# alarm_lamp.net
KiCad netlist of a schematic drawn in EAGLE
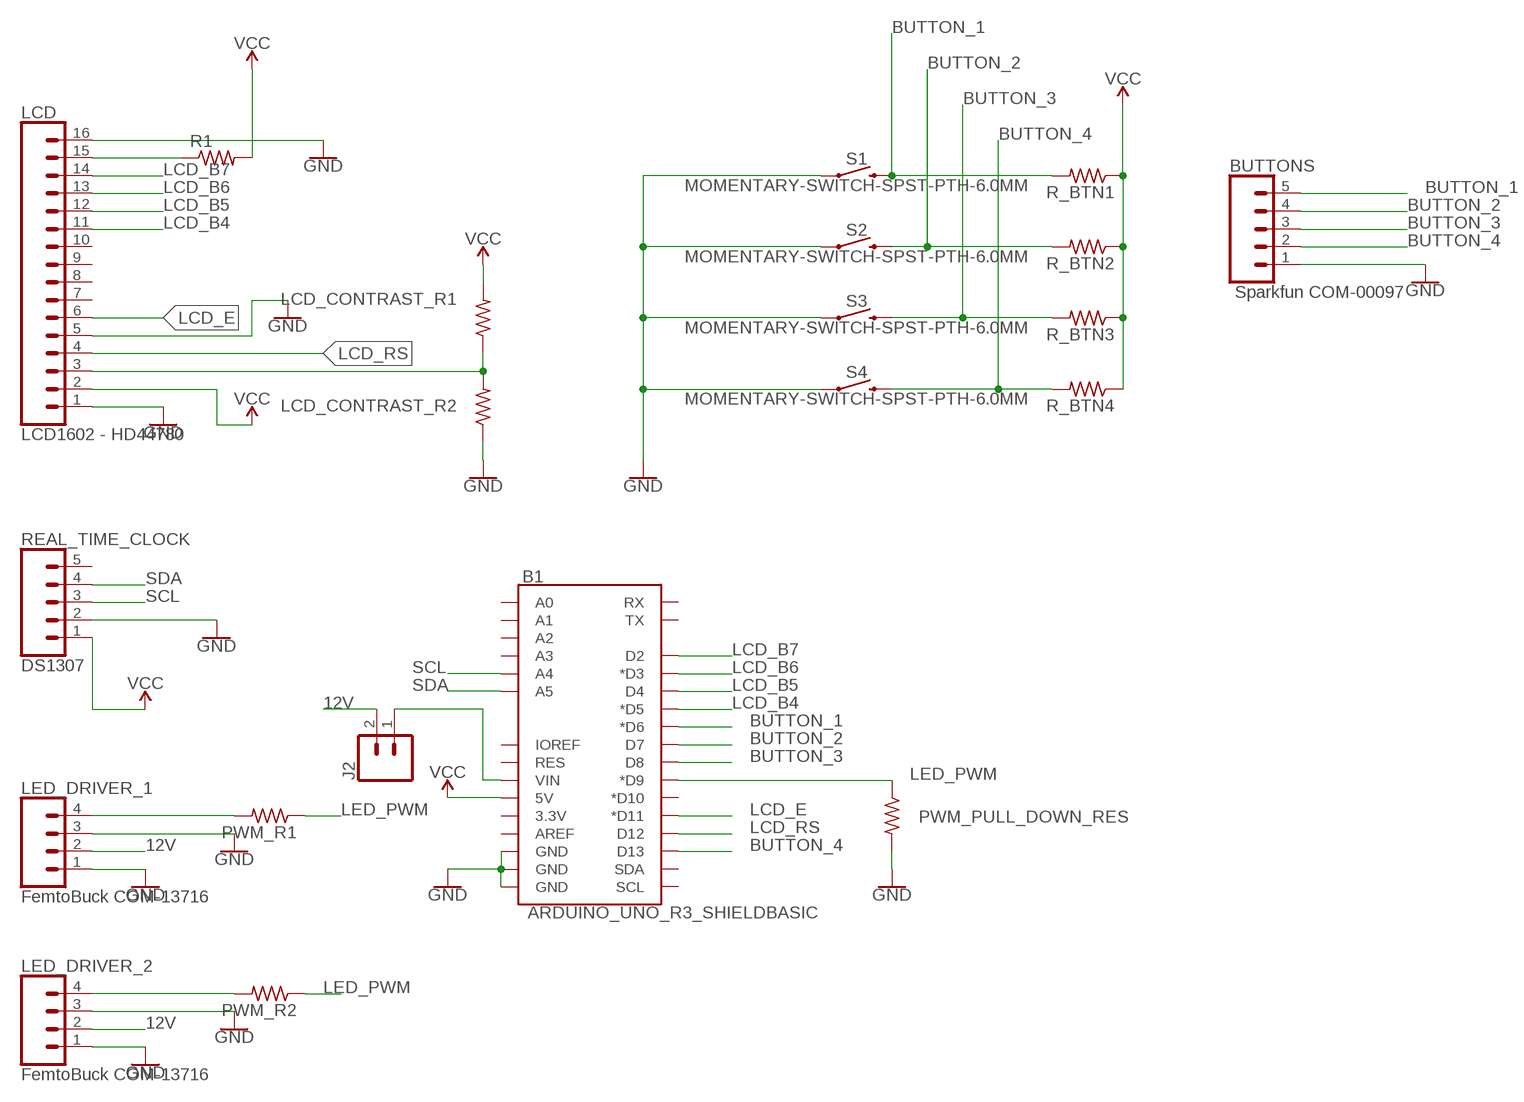
[diagram p0: schematic, sheet 1]
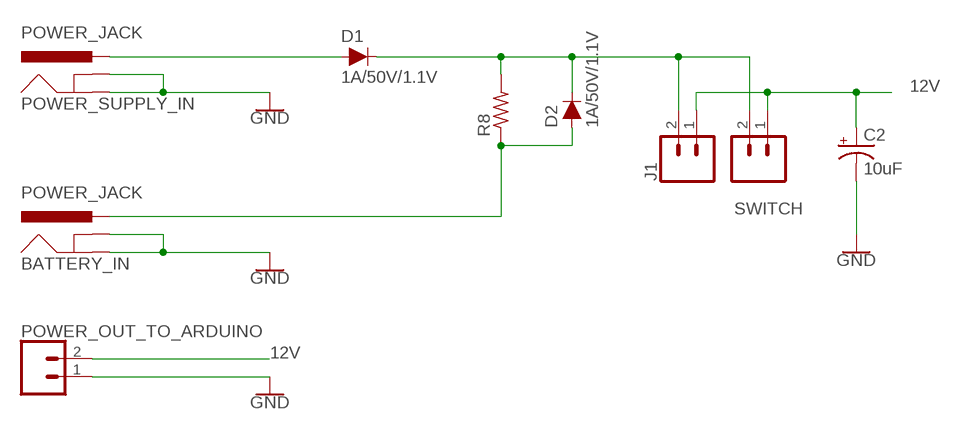
[diagram p1: schematic, sheet 2]

(export (version "E")
  (design (tool "Eeschema 10.0.6"))
  (components
    (comp (ref "B1")
      (value "ARDUINO_UNO_R3_SHIELDBASIC")
      (footprint "eagle-import:UNO_R3_SHIELD")
      (libsource (lib "eagle-import") (part "ARDUINO_UNO_R3_SHIELDBASIC"))
    )
    (comp (ref "BUTTONS")
      (value "Sparkfun COM-00097")
      (footprint "eagle-import:1X05")
      (libsource (lib "eagle-import") (part "CONN_05"))
    )
    (comp (ref "J2")
      (value "CONN_02")
      (footprint "eagle-import:1X02")
      (libsource (lib "eagle-import") (part "CONN_02"))
    )
    (comp (ref "LCD")
      (value "LCD1602 - HD44780")
      (footprint "eagle-import:1X16")
      (libsource (lib "eagle-import") (part "CONN_16"))
    )
    (comp (ref "LCD_CONTRAST_R1")
      (value "R-US_0207/9")
      (footprint "eagle-import:0207_9")
      (libsource (lib "eagle-import") (part "R-US_0207/9"))
    )
    (comp (ref "LCD_CONTRAST_R2")
      (value "R-US_0207/9")
      (footprint "eagle-import:0207_9")
      (libsource (lib "eagle-import") (part "R-US_0207/9"))
    )
    (comp (ref "LED_DRIVER_1")
      (value "FemtoBuck COM-13716")
      (footprint "eagle-import:1X04")
      (libsource (lib "eagle-import") (part "CONN_04"))
    )
    (comp (ref "LED_DRIVER_2")
      (value "FemtoBuck COM-13716")
      (footprint "eagle-import:1X04")
      (libsource (lib "eagle-import") (part "CONN_04"))
    )
    (comp (ref "PWM_PULL_DOWN_RES")
      (value "R-US_0207/9")
      (footprint "eagle-import:0207_9")
      (libsource (lib "eagle-import") (part "R-US_0207/9"))
    )
    (comp (ref "PWM_R1")
      (value "R-US_0207/9")
      (footprint "eagle-import:0207_9")
      (libsource (lib "eagle-import") (part "R-US_0207/9"))
    )
    (comp (ref "PWM_R2")
      (value "R-US_0207/9")
      (footprint "eagle-import:0207_9")
      (libsource (lib "eagle-import") (part "R-US_0207/9"))
    )
    (comp (ref "R1")
      (value "R-US_0207/9")
      (footprint "eagle-import:0207_9")
      (libsource (lib "eagle-import") (part "R-US_0207/9"))
    )
    (comp (ref "REAL_TIME_CLOCK")
      (value "DS1307")
      (footprint "eagle-import:1X05")
      (libsource (lib "eagle-import") (part "CONN_05"))
    )
    (comp (ref "R_BTN1")
      (value "R-US_0207/9")
      (footprint "eagle-import:0207_9")
      (libsource (lib "eagle-import") (part "R-US_0207/9"))
    )
    (comp (ref "R_BTN2")
      (value "R-US_0207/9")
      (footprint "eagle-import:0207_9")
      (libsource (lib "eagle-import") (part "R-US_0207/9"))
    )
    (comp (ref "R_BTN3")
      (value "R-US_0207/9")
      (footprint "eagle-import:0207_9")
      (libsource (lib "eagle-import") (part "R-US_0207/9"))
    )
    (comp (ref "R_BTN4")
      (value "R-US_0207/9")
      (footprint "eagle-import:0207_9")
      (libsource (lib "eagle-import") (part "R-US_0207/9"))
    )
    (comp (ref "S1")
      (value "MOMENTARY-SWITCH-SPST-PTH-6.0MM")
      (footprint "eagle-import:TACTILE_SWITCH_PTH_6.0MM")
      (libsource (lib "eagle-import") (part "MOMENTARY-SWITCH-SPST-PTH-6.0MM"))
    )
    (comp (ref "S2")
      (value "MOMENTARY-SWITCH-SPST-PTH-6.0MM")
      (footprint "eagle-import:TACTILE_SWITCH_PTH_6.0MM")
      (libsource (lib "eagle-import") (part "MOMENTARY-SWITCH-SPST-PTH-6.0MM"))
    )
    (comp (ref "S3")
      (value "MOMENTARY-SWITCH-SPST-PTH-6.0MM")
      (footprint "eagle-import:TACTILE_SWITCH_PTH_6.0MM")
      (libsource (lib "eagle-import") (part "MOMENTARY-SWITCH-SPST-PTH-6.0MM"))
    )
    (comp (ref "S4")
      (value "MOMENTARY-SWITCH-SPST-PTH-6.0MM")
      (footprint "eagle-import:TACTILE_SWITCH_PTH_6.0MM")
      (libsource (lib "eagle-import") (part "MOMENTARY-SWITCH-SPST-PTH-6.0MM"))
    )
    (comp (ref "BATTERY_IN")
      (value "POWER_JACK")
      (footprint "eagle-import:POWER_JACK_PTH")
      (libsource (lib "eagle-import") (part "POWER_JACK"))
    )
    (comp (ref "C2")
      (value "10uF")
      (footprint "eagle-import:CPOL-RADIAL-2.5MM-5MM")
      (libsource (lib "eagle-import") (part "10UF-POLAR-RADIAL-2.5MM-25V-20%"))
    )
    (comp (ref "D1")
      (value "1A/50V/1.1V")
      (footprint "eagle-import:DIODE-1N4001")
      (libsource (lib "eagle-import") (part "DIODE-PTH"))
    )
    (comp (ref "D2")
      (value "1A/50V/1.1V")
      (footprint "eagle-import:DIODE-1N4001")
      (libsource (lib "eagle-import") (part "DIODE-PTH"))
    )
    (comp (ref "J1")
      (value "CONN_02")
      (footprint "eagle-import:1X02")
      (libsource (lib "eagle-import") (part "CONN_02"))
    )
    (comp (ref "POWER_OUT_TO_ARDUINO")
      (value "CONN_023.5MM")
      (footprint "eagle-import:SCREWTERMINAL-3.5MM-2")
      (libsource (lib "eagle-import") (part "CONN_023.5MM"))
    )
    (comp (ref "POWER_SUPPLY_IN")
      (value "POWER_JACK")
      (footprint "eagle-import:POWER_JACK_PTH")
      (libsource (lib "eagle-import") (part "POWER_JACK"))
    )
    (comp (ref "R8")
      (value "R-US_0207/9")
      (footprint "eagle-import:0207_9")
      (libsource (lib "eagle-import") (part "R-US_0207/9"))
    )
    (comp (ref "SWITCH")
      (value "CONN_023.5MM")
      (footprint "eagle-import:SCREWTERMINAL-3.5MM-2")
      (libsource (lib "eagle-import") (part "CONN_023.5MM"))
    )
  )
  (nets
    (net (code "1") (name "12V") (class "Default")
      (node (ref "C2") (pin "1") (pinfunction "+_1") (pintype "passive"))
      (node (ref "J1") (pin "1") (pinfunction "1_1") (pintype "passive"))
      (node (ref "J2") (pin "2") (pinfunction "2_2") (pintype "passive"))
      (node (ref "LED_DRIVER_1") (pin "2") (pinfunction "2_2") (pintype "passive"))
      (node (ref "LED_DRIVER_2") (pin "2") (pinfunction "2_2") (pintype "passive"))
      (node (ref "POWER_OUT_TO_ARDUINO") (pin "2") (pinfunction "2_2") (pintype "passive"))
      (node (ref "SWITCH") (pin "1") (pinfunction "1_1") (pintype "passive"))
    )
    (net (code "2") (name "BUTTON_1") (class "Default")
      (node (ref "B1") (pin "D6") (pinfunction "*D6_D6") (pintype "bidirectional"))
      (node (ref "BUTTONS") (pin "5") (pinfunction "5_5") (pintype "passive"))
      (node (ref "R_BTN1") (pin "2") (pinfunction "2_2") (pintype "passive"))
      (node (ref "S1") (pin "3") (pinfunction "2_3") (pintype "passive"))
    )
    (net (code "3") (name "BUTTON_2") (class "Default")
      (node (ref "B1") (pin "D7") (pinfunction "D7_D7") (pintype "bidirectional"))
      (node (ref "BUTTONS") (pin "4") (pinfunction "4_4") (pintype "passive"))
      (node (ref "R_BTN2") (pin "2") (pinfunction "2_2") (pintype "passive"))
      (node (ref "S2") (pin "3") (pinfunction "2_3") (pintype "passive"))
    )
    (net (code "4") (name "BUTTON_3") (class "Default")
      (node (ref "B1") (pin "D8") (pinfunction "D8_D8") (pintype "bidirectional"))
      (node (ref "BUTTONS") (pin "3") (pinfunction "3_3") (pintype "passive"))
      (node (ref "R_BTN3") (pin "2") (pinfunction "2_2") (pintype "passive"))
      (node (ref "S3") (pin "3") (pinfunction "2_3") (pintype "passive"))
    )
    (net (code "5") (name "BUTTON_4") (class "Default")
      (node (ref "B1") (pin "D13") (pinfunction "D13_D13") (pintype "bidirectional"))
      (node (ref "BUTTONS") (pin "2") (pinfunction "2_2") (pintype "passive"))
      (node (ref "R_BTN4") (pin "2") (pinfunction "2_2") (pintype "passive"))
      (node (ref "S4") (pin "3") (pinfunction "2_3") (pintype "passive"))
    )
    (net (code "6") (name "GND") (class "Default")
      (node (ref "B1") (pin "GND@0") (pinfunction "GND_GND@0") (pintype "bidirectional"))
      (node (ref "B1") (pin "GND@1") (pinfunction "GND_GND@1") (pintype "bidirectional"))
      (node (ref "B1") (pin "GND@2") (pinfunction "GND_GND@2") (pintype "bidirectional"))
      (node (ref "BATTERY_IN") (pin "GND") (pinfunction "GND_GND") (pintype "bidirectional"))
      (node (ref "BATTERY_IN") (pin "GNDBREAK") (pinfunction "GNDBREAK_GNDBREAK") (pintype "bidirectional"))
      (node (ref "BUTTONS") (pin "1") (pinfunction "1_1") (pintype "passive"))
      (node (ref "C2") (pin "2") (pinfunction "-_2") (pintype "passive"))
      (node (ref "LCD") (pin "1") (pinfunction "1_1") (pintype "passive"))
      (node (ref "LCD") (pin "16") (pinfunction "16_16") (pintype "passive"))
      (node (ref "LCD") (pin "5") (pinfunction "5_5") (pintype "passive"))
      (node (ref "LCD_CONTRAST_R2") (pin "1") (pinfunction "1_1") (pintype "passive"))
      (node (ref "LED_DRIVER_1") (pin "1") (pinfunction "1_1") (pintype "passive"))
      (node (ref "LED_DRIVER_1") (pin "3") (pinfunction "3_3") (pintype "passive"))
      (node (ref "LED_DRIVER_2") (pin "1") (pinfunction "1_1") (pintype "passive"))
      (node (ref "LED_DRIVER_2") (pin "3") (pinfunction "3_3") (pintype "passive"))
      (node (ref "POWER_OUT_TO_ARDUINO") (pin "1") (pinfunction "1_1") (pintype "passive"))
      (node (ref "POWER_SUPPLY_IN") (pin "GND") (pinfunction "GND_GND") (pintype "bidirectional"))
      (node (ref "POWER_SUPPLY_IN") (pin "GNDBREAK") (pinfunction "GNDBREAK_GNDBREAK") (pintype "bidirectional"))
      (node (ref "PWM_PULL_DOWN_RES") (pin "2") (pinfunction "2_2") (pintype "passive"))
      (node (ref "REAL_TIME_CLOCK") (pin "2") (pinfunction "2_2") (pintype "passive"))
      (node (ref "S1") (pin "1") (pinfunction "1_1") (pintype "passive"))
      (node (ref "S2") (pin "1") (pinfunction "1_1") (pintype "passive"))
      (node (ref "S3") (pin "1") (pinfunction "1_1") (pintype "passive"))
      (node (ref "S4") (pin "1") (pinfunction "1_1") (pintype "passive"))
    )
    (net (code "7") (name "LCD_B4") (class "Default")
      (node (ref "B1") (pin "D5") (pinfunction "*D5_D5") (pintype "bidirectional"))
      (node (ref "LCD") (pin "11") (pinfunction "11_11") (pintype "passive"))
    )
    (net (code "8") (name "LCD_B5") (class "Default")
      (node (ref "B1") (pin "D4") (pinfunction "D4_D4") (pintype "bidirectional"))
      (node (ref "LCD") (pin "12") (pinfunction "12_12") (pintype "passive"))
    )
    (net (code "9") (name "LCD_B6") (class "Default")
      (node (ref "B1") (pin "D3") (pinfunction "*D3_D3") (pintype "bidirectional"))
      (node (ref "LCD") (pin "13") (pinfunction "13_13") (pintype "passive"))
    )
    (net (code "10") (name "LCD_B7") (class "Default")
      (node (ref "B1") (pin "D2") (pinfunction "D2_D2") (pintype "bidirectional"))
      (node (ref "LCD") (pin "14") (pinfunction "14_14") (pintype "passive"))
    )
    (net (code "11") (name "LCD_E") (class "Default")
      (node (ref "B1") (pin "D11") (pinfunction "*D11_D11") (pintype "bidirectional"))
      (node (ref "LCD") (pin "6") (pinfunction "6_6") (pintype "passive"))
    )
    (net (code "12") (name "LCD_RS") (class "Default")
      (node (ref "B1") (pin "D12") (pinfunction "D12_D12") (pintype "bidirectional"))
      (node (ref "LCD") (pin "4") (pinfunction "4_4") (pintype "passive"))
    )
    (net (code "13") (name "LED_PWM") (class "Default")
      (node (ref "B1") (pin "D9") (pinfunction "*D9_D9") (pintype "bidirectional"))
      (node (ref "PWM_PULL_DOWN_RES") (pin "1") (pinfunction "1_1") (pintype "passive"))
      (node (ref "PWM_R1") (pin "1") (pinfunction "1_1") (pintype "passive"))
      (node (ref "PWM_R2") (pin "1") (pinfunction "1_1") (pintype "passive"))
    )
    (net (code "14") (name "Net-(B1-PadVIN)") (class "Default")
      (node (ref "B1") (pin "VIN") (pinfunction "VIN_VIN") (pintype "bidirectional"))
      (node (ref "J2") (pin "1") (pinfunction "1_1") (pintype "passive"))
    )
    (net (code "15") (name "Net-(BATTERY_IN-PadPWR)") (class "Default")
      (node (ref "BATTERY_IN") (pin "PWR") (pinfunction "PWR_PWR") (pintype "bidirectional"))
      (node (ref "D2") (pin "A") (pinfunction "A_A") (pintype "passive"))
      (node (ref "R8") (pin "1") (pinfunction "1_1") (pintype "passive"))
    )
    (net (code "16") (name "Net-(D1-PadA)") (class "Default")
      (node (ref "D1") (pin "A") (pinfunction "A_A") (pintype "passive"))
      (node (ref "POWER_SUPPLY_IN") (pin "PWR") (pinfunction "PWR_PWR") (pintype "bidirectional"))
    )
    (net (code "17") (name "Net-(D1-PadC)") (class "Default")
      (node (ref "D1") (pin "C") (pinfunction "C_C") (pintype "passive"))
      (node (ref "D2") (pin "C") (pinfunction "C_C") (pintype "passive"))
      (node (ref "J1") (pin "2") (pinfunction "2_2") (pintype "passive"))
      (node (ref "R8") (pin "2") (pinfunction "2_2") (pintype "passive"))
      (node (ref "SWITCH") (pin "2") (pinfunction "2_2") (pintype "passive"))
    )
    (net (code "18") (name "Net-(LCD-Pad3)") (class "Default")
      (node (ref "LCD") (pin "3") (pinfunction "3_3") (pintype "passive"))
      (node (ref "LCD_CONTRAST_R1") (pin "1") (pinfunction "1_1") (pintype "passive"))
      (node (ref "LCD_CONTRAST_R2") (pin "2") (pinfunction "2_2") (pintype "passive"))
    )
    (net (code "19") (name "Net-(LCD-Pad15)") (class "Default")
      (node (ref "LCD") (pin "15") (pinfunction "15_15") (pintype "passive"))
      (node (ref "R1") (pin "1") (pinfunction "1_1") (pintype "passive"))
    )
    (net (code "20") (name "Net-(LED_DRIVER_1-Pad4)") (class "Default")
      (node (ref "LED_DRIVER_1") (pin "4") (pinfunction "4_4") (pintype "passive"))
      (node (ref "PWM_R1") (pin "2") (pinfunction "2_2") (pintype "passive"))
    )
    (net (code "21") (name "Net-(LED_DRIVER_2-Pad4)") (class "Default")
      (node (ref "LED_DRIVER_2") (pin "4") (pinfunction "4_4") (pintype "passive"))
      (node (ref "PWM_R2") (pin "2") (pinfunction "2_2") (pintype "passive"))
    )
    (net (code "22") (name "SCL") (class "Default")
      (node (ref "B1") (pin "A4") (pinfunction "A4_A4") (pintype "bidirectional"))
      (node (ref "REAL_TIME_CLOCK") (pin "3") (pinfunction "3_3") (pintype "passive"))
    )
    (net (code "23") (name "SDA") (class "Default")
      (node (ref "B1") (pin "A5") (pinfunction "A5_A5") (pintype "bidirectional"))
      (node (ref "REAL_TIME_CLOCK") (pin "4") (pinfunction "4_4") (pintype "passive"))
    )
    (net (code "24") (name "VCC") (class "Default")
      (node (ref "B1") (pin "5V") (pinfunction "5V_5V") (pintype "bidirectional"))
      (node (ref "LCD") (pin "2") (pinfunction "2_2") (pintype "passive"))
      (node (ref "LCD_CONTRAST_R1") (pin "2") (pinfunction "2_2") (pintype "passive"))
      (node (ref "R1") (pin "2") (pinfunction "2_2") (pintype "passive"))
      (node (ref "REAL_TIME_CLOCK") (pin "1") (pinfunction "1_1") (pintype "passive"))
      (node (ref "R_BTN1") (pin "1") (pinfunction "1_1") (pintype "passive"))
      (node (ref "R_BTN2") (pin "1") (pinfunction "1_1") (pintype "passive"))
      (node (ref "R_BTN3") (pin "1") (pinfunction "1_1") (pintype "passive"))
      (node (ref "R_BTN4") (pin "1") (pinfunction "1_1") (pintype "passive"))
    )
    (net (code "25") (name "unconnected-(B1-*D10-PadD10)") (class "Default")
      (node (ref "B1") (pin "D10") (pinfunction "*D10_D10") (pintype "bidirectional"))
    )
    (net (code "26") (name "unconnected-(B1-Pad3.3V)") (class "Default")
      (node (ref "B1") (pin "3.3V") (pinfunction "3.3V_3.3V") (pintype "bidirectional"))
    )
    (net (code "27") (name "unconnected-(B1-PadA0)") (class "Default")
      (node (ref "B1") (pin "A0") (pinfunction "A0_A0") (pintype "bidirectional"))
    )
    (net (code "28") (name "unconnected-(B1-PadA1)") (class "Default")
      (node (ref "B1") (pin "A1") (pinfunction "A1_A1") (pintype "bidirectional"))
    )
    (net (code "29") (name "unconnected-(B1-PadA2)") (class "Default")
      (node (ref "B1") (pin "A2") (pinfunction "A2_A2") (pintype "bidirectional"))
    )
    (net (code "30") (name "unconnected-(B1-PadA3)") (class "Default")
      (node (ref "B1") (pin "A3") (pinfunction "A3_A3") (pintype "bidirectional"))
    )
    (net (code "31") (name "unconnected-(B1-PadAREF)") (class "Default")
      (node (ref "B1") (pin "AREF") (pinfunction "AREF_AREF") (pintype "bidirectional"))
    )
    (net (code "32") (name "unconnected-(B1-PadIOREF)") (class "Default")
      (node (ref "B1") (pin "IOREF") (pinfunction "IOREF_IOREF") (pintype "bidirectional"))
    )
    (net (code "33") (name "unconnected-(B1-PadRES)") (class "Default")
      (node (ref "B1") (pin "RES") (pinfunction "RES_RES") (pintype "bidirectional"))
    )
    (net (code "34") (name "unconnected-(B1-PadRX)") (class "Default")
      (node (ref "B1") (pin "RX") (pinfunction "RX_RX") (pintype "bidirectional"))
    )
    (net (code "35") (name "unconnected-(B1-PadSCL)") (class "Default")
      (node (ref "B1") (pin "SCL") (pinfunction "SCL_SCL") (pintype "bidirectional"))
    )
    (net (code "36") (name "unconnected-(B1-PadSDA)") (class "Default")
      (node (ref "B1") (pin "SDA") (pinfunction "SDA_SDA") (pintype "bidirectional"))
    )
    (net (code "37") (name "unconnected-(B1-PadTX)") (class "Default")
      (node (ref "B1") (pin "TX") (pinfunction "TX_TX") (pintype "bidirectional"))
    )
    (net (code "38") (name "unconnected-(LCD-Pad7)") (class "Default")
      (node (ref "LCD") (pin "7") (pinfunction "7_7") (pintype "passive"))
    )
    (net (code "39") (name "unconnected-(LCD-Pad8)") (class "Default")
      (node (ref "LCD") (pin "8") (pinfunction "8_8") (pintype "passive"))
    )
    (net (code "40") (name "unconnected-(LCD-Pad9)") (class "Default")
      (node (ref "LCD") (pin "9") (pinfunction "9_9") (pintype "passive"))
    )
    (net (code "41") (name "unconnected-(LCD-Pad10)") (class "Default")
      (node (ref "LCD") (pin "10") (pinfunction "10_10") (pintype "passive"))
    )
    (net (code "42") (name "unconnected-(REAL_TIME_CLOCK-Pad5)") (class "Default")
      (node (ref "REAL_TIME_CLOCK") (pin "5") (pinfunction "5_5") (pintype "passive"))
    )
  )
)
